# led_pack32.net
KiCad netlist of a schematic drawn in Altium Designer
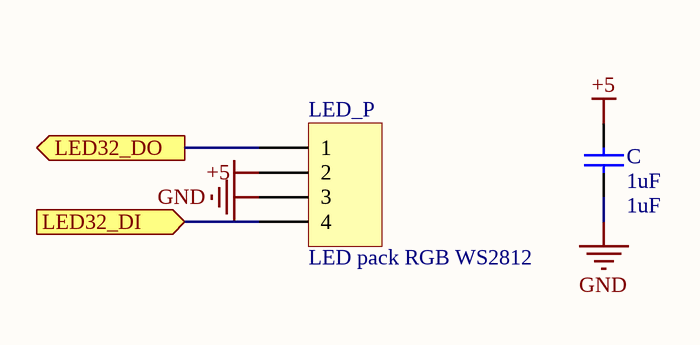
[diagram p0: led_pack32.SchDoc]

(export (version "E")
  (design (tool "Eeschema 10.0.6"))
  (components
    (comp (ref "C")
      (value "1uF")
      (footprint "0603C")
      (description "CAP SMD 0603")
      (fields (field (name "ALTIUM_VALUE") "1uF") (field (name "PUBLISHER") "Altium Limited"))
      (libsource (lib "Miscellaneous Devices") (part "Cap"))
    )
    (comp (ref "LED_P")
      (value "LED pack RGB WS2812")
      (footprint "pack21-2121")
      (description "5 RGB LED pack")
      (fields (field (name "PUBLISHER") "Altium Limited"))
      (libsource (lib "Altium") (part "Header 4"))
    )
  )
  (nets
    (net (code "1") (name "+5") (class "Default")
      (node (ref "C") (pin "2") (pinfunction "2_2") (pintype "passive"))
      (node (ref "LED_P") (pin "2") (pinfunction "2_2") (pintype "passive"))
    )
    (net (code "2") (name "/LED21_DI") (class "Default")
      (node (ref "LED_P") (pin "4") (pinfunction "4_4") (pintype "passive"))
    )
    (net (code "3") (name "/LED21_DO") (class "Default")
      (node (ref "LED_P") (pin "1") (pinfunction "1_1") (pintype "passive"))
    )
    (net (code "4") (name "GND") (class "Default")
      (node (ref "C") (pin "1") (pinfunction "1_1") (pintype "passive"))
      (node (ref "LED_P") (pin "3") (pinfunction "3_3") (pintype "passive"))
    )
  )
)
